# PCA9685-4conns.net
KiCad netlist of a schematic drawn in EAGLE
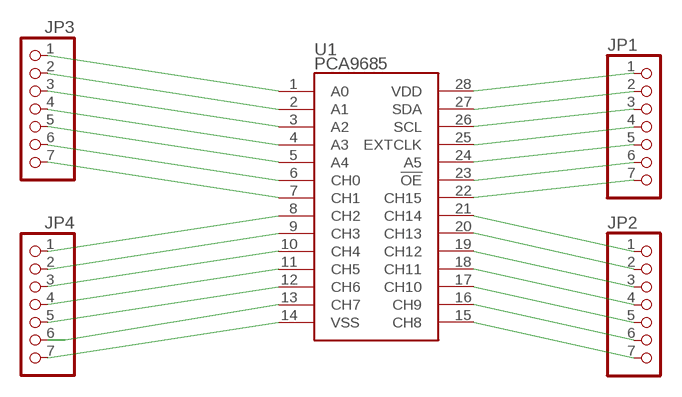
[diagram p0: schematic, sheet 1]

(export (version "E")
  (design (tool "Eeschema 10.0.6"))
  (components
    (comp (ref "JP1")
      (value "PINHD-1X7")
      (footprint "eagle-import:1X07")
      (libsource (lib "eagle-import") (part "PINHD-1X7"))
    )
    (comp (ref "JP2")
      (value "PINHD-1X7")
      (footprint "eagle-import:1X07")
      (libsource (lib "eagle-import") (part "PINHD-1X7"))
    )
    (comp (ref "JP3")
      (value "PINHD-1X7")
      (footprint "eagle-import:1X07")
      (libsource (lib "eagle-import") (part "PINHD-1X7"))
    )
    (comp (ref "JP4")
      (value "PINHD-1X7")
      (footprint "eagle-import:1X07")
      (libsource (lib "eagle-import") (part "PINHD-1X7"))
    )
    (comp (ref "U1")
      (value "PCA9685")
      (footprint "eagle-import:TSSOP-28_4MM")
      (libsource (lib "eagle-import") (part "PCA9685"))
    )
  )
  (nets
    (net (code "1") (name "Net-(U1-A0)") (class "Default")
      (node (ref "JP3") (pin "1") (pinfunction "1_1") (pintype "passive"))
      (node (ref "U1") (pin "1") (pinfunction "A0_1") (pintype "bidirectional"))
    )
    (net (code "2") (name "Net-(U1-A1)") (class "Default")
      (node (ref "JP3") (pin "2") (pinfunction "2_2") (pintype "passive"))
      (node (ref "U1") (pin "2") (pinfunction "A1_2") (pintype "bidirectional"))
    )
    (net (code "3") (name "Net-(U1-A2)") (class "Default")
      (node (ref "JP3") (pin "3") (pinfunction "3_3") (pintype "passive"))
      (node (ref "U1") (pin "3") (pinfunction "A2_3") (pintype "bidirectional"))
    )
    (net (code "4") (name "Net-(U1-A3)") (class "Default")
      (node (ref "JP3") (pin "4") (pinfunction "4_4") (pintype "passive"))
      (node (ref "U1") (pin "4") (pinfunction "A3_4") (pintype "bidirectional"))
    )
    (net (code "5") (name "Net-(U1-A4)") (class "Default")
      (node (ref "JP3") (pin "5") (pinfunction "5_5") (pintype "passive"))
      (node (ref "U1") (pin "5") (pinfunction "A4_5") (pintype "bidirectional"))
    )
    (net (code "6") (name "Net-(U1-A5)") (class "Default")
      (node (ref "JP1") (pin "5") (pinfunction "5_5") (pintype "passive"))
      (node (ref "U1") (pin "24") (pinfunction "A5_24") (pintype "bidirectional"))
    )
    (net (code "7") (name "Net-(U1-CH0)") (class "Default")
      (node (ref "JP3") (pin "6") (pinfunction "6_6") (pintype "passive"))
      (node (ref "U1") (pin "6") (pinfunction "CH0_6") (pintype "bidirectional"))
    )
    (net (code "8") (name "Net-(U1-CH1)") (class "Default")
      (node (ref "JP3") (pin "7") (pinfunction "7_7") (pintype "passive"))
      (node (ref "U1") (pin "7") (pinfunction "CH1_7") (pintype "bidirectional"))
    )
    (net (code "9") (name "Net-(U1-CH2)") (class "Default")
      (node (ref "JP4") (pin "1") (pinfunction "1_1") (pintype "passive"))
      (node (ref "U1") (pin "8") (pinfunction "CH2_8") (pintype "bidirectional"))
    )
    (net (code "10") (name "Net-(U1-CH3)") (class "Default")
      (node (ref "JP4") (pin "2") (pinfunction "2_2") (pintype "passive"))
      (node (ref "U1") (pin "9") (pinfunction "CH3_9") (pintype "bidirectional"))
    )
    (net (code "11") (name "Net-(U1-CH4)") (class "Default")
      (node (ref "JP4") (pin "3") (pinfunction "3_3") (pintype "passive"))
      (node (ref "U1") (pin "10") (pinfunction "CH4_10") (pintype "bidirectional"))
    )
    (net (code "12") (name "Net-(U1-CH5)") (class "Default")
      (node (ref "JP4") (pin "4") (pinfunction "4_4") (pintype "passive"))
      (node (ref "U1") (pin "11") (pinfunction "CH5_11") (pintype "bidirectional"))
    )
    (net (code "13") (name "Net-(U1-CH6)") (class "Default")
      (node (ref "JP4") (pin "5") (pinfunction "5_5") (pintype "passive"))
      (node (ref "U1") (pin "12") (pinfunction "CH6_12") (pintype "bidirectional"))
    )
    (net (code "14") (name "Net-(U1-CH7)") (class "Default")
      (node (ref "JP4") (pin "6") (pinfunction "6_6") (pintype "passive"))
      (node (ref "U1") (pin "13") (pinfunction "CH7_13") (pintype "bidirectional"))
    )
    (net (code "15") (name "Net-(U1-CH8)") (class "Default")
      (node (ref "JP2") (pin "7") (pinfunction "7_7") (pintype "passive"))
      (node (ref "U1") (pin "15") (pinfunction "CH8_15") (pintype "bidirectional"))
    )
    (net (code "16") (name "Net-(U1-CH9)") (class "Default")
      (node (ref "JP2") (pin "6") (pinfunction "6_6") (pintype "passive"))
      (node (ref "U1") (pin "16") (pinfunction "CH9_16") (pintype "bidirectional"))
    )
    (net (code "17") (name "Net-(U1-CH10)") (class "Default")
      (node (ref "JP2") (pin "5") (pinfunction "5_5") (pintype "passive"))
      (node (ref "U1") (pin "17") (pinfunction "CH10_17") (pintype "bidirectional"))
    )
    (net (code "18") (name "Net-(U1-CH11)") (class "Default")
      (node (ref "JP2") (pin "4") (pinfunction "4_4") (pintype "passive"))
      (node (ref "U1") (pin "18") (pinfunction "CH11_18") (pintype "bidirectional"))
    )
    (net (code "19") (name "Net-(U1-CH12)") (class "Default")
      (node (ref "JP2") (pin "3") (pinfunction "3_3") (pintype "passive"))
      (node (ref "U1") (pin "19") (pinfunction "CH12_19") (pintype "bidirectional"))
    )
    (net (code "20") (name "Net-(U1-CH13)") (class "Default")
      (node (ref "JP2") (pin "2") (pinfunction "2_2") (pintype "passive"))
      (node (ref "U1") (pin "20") (pinfunction "CH13_20") (pintype "bidirectional"))
    )
    (net (code "21") (name "Net-(U1-CH14)") (class "Default")
      (node (ref "JP2") (pin "1") (pinfunction "1_1") (pintype "passive"))
      (node (ref "U1") (pin "21") (pinfunction "CH14_21") (pintype "bidirectional"))
    )
    (net (code "22") (name "Net-(U1-CH15)") (class "Default")
      (node (ref "JP1") (pin "7") (pinfunction "7_7") (pintype "passive"))
      (node (ref "U1") (pin "22") (pinfunction "CH15_22") (pintype "bidirectional"))
    )
    (net (code "23") (name "Net-(U1-EXTCLK)") (class "Default")
      (node (ref "JP1") (pin "4") (pinfunction "4_4") (pintype "passive"))
      (node (ref "U1") (pin "25") (pinfunction "EXTCLK_25") (pintype "bidirectional"))
    )
    (net (code "24") (name "Net-(U1-SCL)") (class "Default")
      (node (ref "JP1") (pin "3") (pinfunction "3_3") (pintype "passive"))
      (node (ref "U1") (pin "26") (pinfunction "SCL_26") (pintype "bidirectional"))
    )
    (net (code "25") (name "Net-(U1-SDA)") (class "Default")
      (node (ref "JP1") (pin "2") (pinfunction "2_2") (pintype "passive"))
      (node (ref "U1") (pin "27") (pinfunction "SDA_27") (pintype "bidirectional"))
    )
    (net (code "26") (name "Net-(U1-VDD)") (class "Default")
      (node (ref "JP1") (pin "1") (pinfunction "1_1") (pintype "passive"))
      (node (ref "U1") (pin "28") (pinfunction "VDD_28") (pintype "bidirectional"))
    )
    (net (code "27") (name "Net-(U1-VSS)") (class "Default")
      (node (ref "JP4") (pin "7") (pinfunction "7_7") (pintype "passive"))
      (node (ref "U1") (pin "14") (pinfunction "VSS_14") (pintype "bidirectional"))
    )
    (net (code "28") (name "Net-(U1-~{OE})") (class "Default")
      (node (ref "JP1") (pin "6") (pinfunction "6_6") (pintype "passive"))
      (node (ref "U1") (pin "23") (pinfunction "~{OE}_23") (pintype "bidirectional"))
    )
  )
)
